# MotherBoard_ver2_2.net
KiCad netlist of a schematic drawn in EAGLE
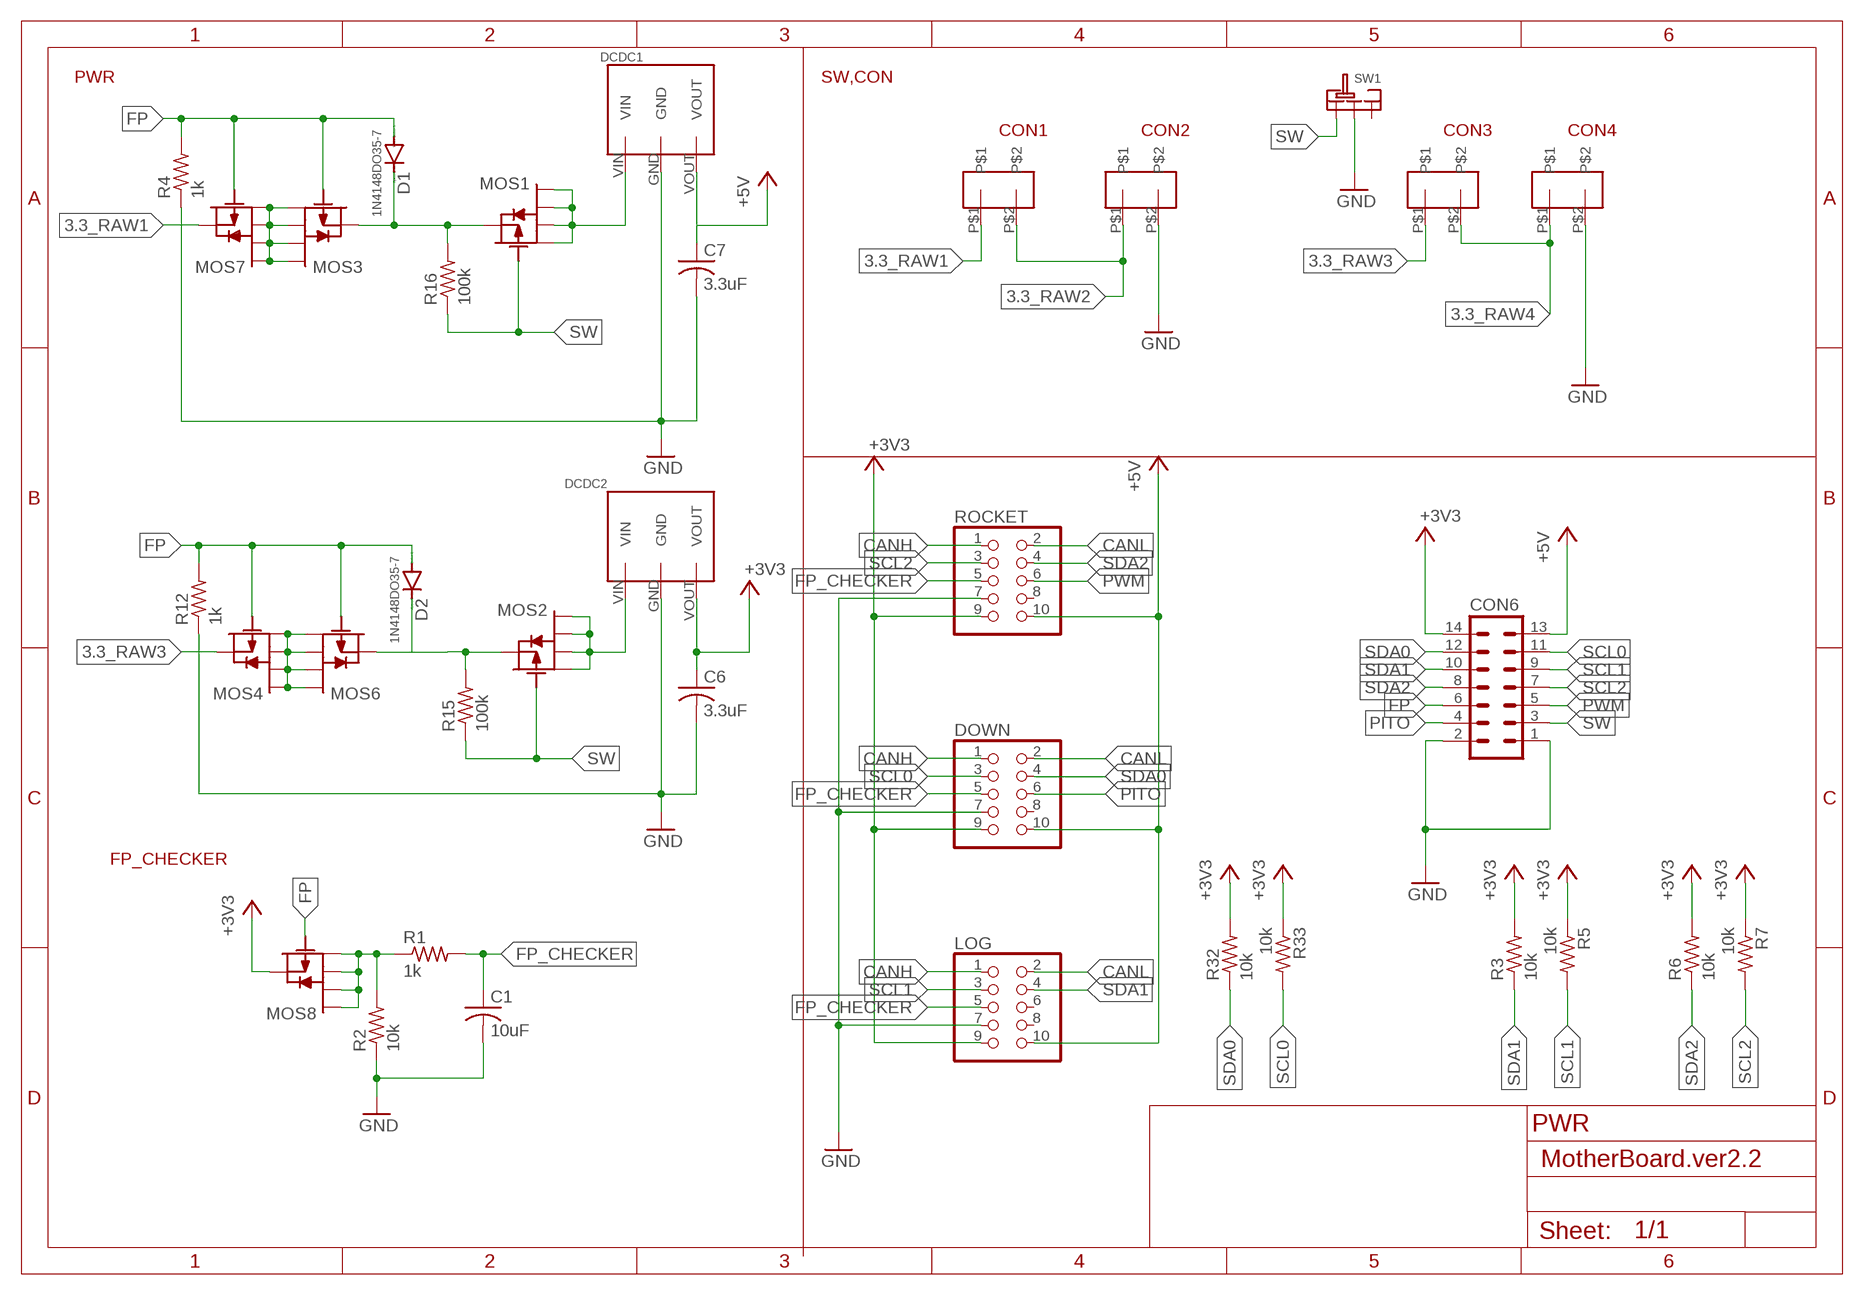
[diagram p0: schematic, sheet 1]

(export (version "E")
  (design (tool "Eeschema 10.0.6"))
  (components
    (comp (ref "C1")
      (value "10uF")
      (footprint "eagle-import:C0603")
      (libsource (lib "eagle-import") (part "C-USC0603"))
    )
    (comp (ref "C6")
      (value "3.3uF")
      (footprint "eagle-import:C0603")
      (libsource (lib "eagle-import") (part "C-USC0603"))
    )
    (comp (ref "C7")
      (value "3.3uF")
      (footprint "eagle-import:C0603")
      (libsource (lib "eagle-import") (part "C-USC0603"))
    )
    (comp (ref "CON1")
      (value "1.25CON2PIN")
      (footprint "eagle-import:1.25CON2PIN")
      (libsource (lib "eagle-import") (part "1.25CON2PIN"))
    )
    (comp (ref "CON2")
      (value "1.25CON2PIN")
      (footprint "eagle-import:1.25CON2PIN")
      (libsource (lib "eagle-import") (part "1.25CON2PIN"))
    )
    (comp (ref "CON3")
      (value "1.25CON2PIN")
      (footprint "eagle-import:1.25CON2PIN")
      (libsource (lib "eagle-import") (part "1.25CON2PIN"))
    )
    (comp (ref "CON4")
      (value "1.25CON2PIN")
      (footprint "eagle-import:1.25CON2PIN")
      (libsource (lib "eagle-import") (part "1.25CON2PIN"))
    )
    (comp (ref "CON6")
      (value "ML14L")
      (footprint "eagle-import:ML14L")
      (libsource (lib "eagle-import") (part "ML14L"))
    )
    (comp (ref "D1")
      (value "1N4148DO35-7")
      (footprint "eagle-import:DO35-7")
      (libsource (lib "eagle-import") (part "1N4148DO35-7"))
    )
    (comp (ref "D2")
      (value "1N4148DO35-7")
      (footprint "eagle-import:DO35-7")
      (libsource (lib "eagle-import") (part "1N4148DO35-7"))
    )
    (comp (ref "DCDC1")
      (value "5V1A_M78AR05-1")
      (footprint "eagle-import:5V1A_M78AR05-1")
      (libsource (lib "eagle-import") (part "5V1A_M78AR05-1"))
    )
    (comp (ref "DCDC2")
      (value "3.3V1A_M78AR033-1")
      (footprint "eagle-import:3.3V1A_M78AR033-1")
      (libsource (lib "eagle-import") (part "3.3V1A_M78AR033-1"))
    )
    (comp (ref "DOWN")
      (value "PINHD-2X5")
      (footprint "eagle-import:2X05")
      (libsource (lib "eagle-import") (part "PINHD-2X5"))
    )
    (comp (ref "LOG")
      (value "PINHD-2X5")
      (footprint "eagle-import:2X05")
      (libsource (lib "eagle-import") (part "PINHD-2X5"))
    )
    (comp (ref "MOS1")
      (value "PCH_SSM6J808R")
      (footprint "eagle-import:SSM6J808R")
      (libsource (lib "eagle-import") (part "PCH_SSM6J808R"))
    )
    (comp (ref "MOS2")
      (value "PCH_SSM6J808R")
      (footprint "eagle-import:SSM6J808R")
      (libsource (lib "eagle-import") (part "PCH_SSM6J808R"))
    )
    (comp (ref "MOS3")
      (value "PCH_SSM6J808R")
      (footprint "eagle-import:SSM6J808R")
      (libsource (lib "eagle-import") (part "PCH_SSM6J808R"))
    )
    (comp (ref "MOS4")
      (value "PCH_SSM6J808R")
      (footprint "eagle-import:SSM6J808R")
      (libsource (lib "eagle-import") (part "PCH_SSM6J808R"))
    )
    (comp (ref "MOS6")
      (value "PCH_SSM6J808R")
      (footprint "eagle-import:SSM6J808R")
      (libsource (lib "eagle-import") (part "PCH_SSM6J808R"))
    )
    (comp (ref "MOS7")
      (value "PCH_SSM6J808R")
      (footprint "eagle-import:SSM6J808R")
      (libsource (lib "eagle-import") (part "PCH_SSM6J808R"))
    )
    (comp (ref "MOS8")
      (value "PCH_SSM6J808R")
      (footprint "eagle-import:SSM6J808R")
      (libsource (lib "eagle-import") (part "PCH_SSM6J808R"))
    )
    (comp (ref "R1")
      (value "1k")
      (footprint "eagle-import:R0603")
      (libsource (lib "eagle-import") (part "R-US_R0603"))
    )
    (comp (ref "R2")
      (value "10k")
      (footprint "eagle-import:R0603")
      (libsource (lib "eagle-import") (part "R-US_R0603"))
    )
    (comp (ref "R3")
      (value "10k")
      (footprint "eagle-import:R0603")
      (libsource (lib "eagle-import") (part "R-US_R0603"))
    )
    (comp (ref "R4")
      (value "1k")
      (footprint "eagle-import:R0603")
      (libsource (lib "eagle-import") (part "R-US_R0603"))
    )
    (comp (ref "R5")
      (value "10k")
      (footprint "eagle-import:R0603")
      (libsource (lib "eagle-import") (part "R-US_R0603"))
    )
    (comp (ref "R6")
      (value "10k")
      (footprint "eagle-import:R0603")
      (libsource (lib "eagle-import") (part "R-US_R0603"))
    )
    (comp (ref "R7")
      (value "10k")
      (footprint "eagle-import:R0603")
      (libsource (lib "eagle-import") (part "R-US_R0603"))
    )
    (comp (ref "R12")
      (value "1k")
      (footprint "eagle-import:R0603")
      (libsource (lib "eagle-import") (part "R-US_R0603"))
    )
    (comp (ref "R15")
      (value "100k")
      (footprint "eagle-import:R0603")
      (libsource (lib "eagle-import") (part "R-US_R0603"))
    )
    (comp (ref "R16")
      (value "100k")
      (footprint "eagle-import:R0603")
      (libsource (lib "eagle-import") (part "R-US_R0603"))
    )
    (comp (ref "R32")
      (value "10k")
      (footprint "eagle-import:R0603")
      (libsource (lib "eagle-import") (part "R-US_R0603"))
    )
    (comp (ref "R33")
      (value "10k")
      (footprint "eagle-import:R0603")
      (libsource (lib "eagle-import") (part "R-US_R0603"))
    )
    (comp (ref "ROCKET")
      (value "PINHD-2X5")
      (footprint "eagle-import:2X05")
      (libsource (lib "eagle-import") (part "PINHD-2X5"))
    )
    (comp (ref "SW1")
      (value "SRIDE_SWITCH")
      (footprint "eagle-import:SRIDE_SWITCH")
      (libsource (lib "eagle-import") (part "SRIDE_SWITCH"))
    )
  )
  (nets
    (net (code "1") (name "+3V3") (class "Default")
      (node (ref "C6") (pin "1") (pinfunction "1_1") (pintype "passive"))
      (node (ref "CON6") (pin "14") (pinfunction "14_14") (pintype "passive"))
      (node (ref "DCDC2") (pin "VOUT") (pinfunction "VOUT_VOUT") (pintype "bidirectional"))
      (node (ref "DOWN") (pin "9") (pinfunction "9_9") (pintype "passive"))
      (node (ref "LOG") (pin "9") (pinfunction "9_9") (pintype "passive"))
      (node (ref "MOS8") (pin "4") (pinfunction "4_4") (pintype "bidirectional"))
      (node (ref "R3") (pin "2") (pinfunction "2_2") (pintype "passive"))
      (node (ref "R32") (pin "2") (pinfunction "2_2") (pintype "passive"))
      (node (ref "R33") (pin "1") (pinfunction "1_1") (pintype "passive"))
      (node (ref "R5") (pin "1") (pinfunction "1_1") (pintype "passive"))
      (node (ref "R6") (pin "2") (pinfunction "2_2") (pintype "passive"))
      (node (ref "R7") (pin "1") (pinfunction "1_1") (pintype "passive"))
      (node (ref "ROCKET") (pin "9") (pinfunction "9_9") (pintype "passive"))
    )
    (net (code "2") (name "+5V") (class "Default")
      (node (ref "C7") (pin "1") (pinfunction "1_1") (pintype "passive"))
      (node (ref "CON6") (pin "13") (pinfunction "13_13") (pintype "passive"))
      (node (ref "DCDC1") (pin "VOUT") (pinfunction "VOUT_VOUT") (pintype "bidirectional"))
      (node (ref "DOWN") (pin "10") (pinfunction "10_10") (pintype "passive"))
      (node (ref "LOG") (pin "10") (pinfunction "10_10") (pintype "passive"))
      (node (ref "ROCKET") (pin "10") (pinfunction "10_10") (pintype "passive"))
    )
    (net (code "3") (name "3.3_RAW1") (class "Default")
      (node (ref "CON1") (pin "P$1") (pinfunction "P$1_P$1") (pintype "bidirectional"))
      (node (ref "MOS7") (pin "4") (pinfunction "4_4") (pintype "bidirectional"))
    )
    (net (code "4") (name "3.3_RAW2") (class "Default")
      (node (ref "CON1") (pin "P$2") (pinfunction "P$2_P$2") (pintype "bidirectional"))
      (node (ref "CON2") (pin "P$1") (pinfunction "P$1_P$1") (pintype "bidirectional"))
    )
    (net (code "5") (name "3.3_RAW3") (class "Default")
      (node (ref "CON3") (pin "P$1") (pinfunction "P$1_P$1") (pintype "bidirectional"))
      (node (ref "MOS4") (pin "4") (pinfunction "4_4") (pintype "bidirectional"))
    )
    (net (code "6") (name "3.3_RAW4") (class "Default")
      (node (ref "CON3") (pin "P$2") (pinfunction "P$2_P$2") (pintype "bidirectional"))
      (node (ref "CON4") (pin "P$1") (pinfunction "P$1_P$1") (pintype "bidirectional"))
    )
    (net (code "7") (name "CANH") (class "Default")
      (node (ref "DOWN") (pin "1") (pinfunction "1_1") (pintype "passive"))
      (node (ref "LOG") (pin "1") (pinfunction "1_1") (pintype "passive"))
      (node (ref "ROCKET") (pin "1") (pinfunction "1_1") (pintype "passive"))
    )
    (net (code "8") (name "CANL") (class "Default")
      (node (ref "DOWN") (pin "2") (pinfunction "2_2") (pintype "passive"))
      (node (ref "LOG") (pin "2") (pinfunction "2_2") (pintype "passive"))
      (node (ref "ROCKET") (pin "2") (pinfunction "2_2") (pintype "passive"))
    )
    (net (code "9") (name "FP") (class "Default")
      (node (ref "CON6") (pin "6") (pinfunction "6_6") (pintype "passive"))
      (node (ref "D1") (pin "A") (pinfunction "A_A") (pintype "passive"))
      (node (ref "D2") (pin "A") (pinfunction "A_A") (pintype "passive"))
      (node (ref "MOS3") (pin "3") (pinfunction "3_3") (pintype "bidirectional"))
      (node (ref "MOS4") (pin "3") (pinfunction "3_3") (pintype "bidirectional"))
      (node (ref "MOS6") (pin "3") (pinfunction "3_3") (pintype "bidirectional"))
      (node (ref "MOS7") (pin "3") (pinfunction "3_3") (pintype "bidirectional"))
      (node (ref "MOS8") (pin "3") (pinfunction "3_3") (pintype "bidirectional"))
      (node (ref "R12") (pin "2") (pinfunction "2_2") (pintype "passive"))
      (node (ref "R4") (pin "2") (pinfunction "2_2") (pintype "passive"))
    )
    (net (code "10") (name "FP_CHECKER") (class "Default")
      (node (ref "C1") (pin "1") (pinfunction "1_1") (pintype "passive"))
      (node (ref "DOWN") (pin "5") (pinfunction "5_5") (pintype "passive"))
      (node (ref "LOG") (pin "5") (pinfunction "5_5") (pintype "passive"))
      (node (ref "R1") (pin "2") (pinfunction "2_2") (pintype "passive"))
      (node (ref "ROCKET") (pin "5") (pinfunction "5_5") (pintype "passive"))
    )
    (net (code "11") (name "GND") (class "Default")
      (node (ref "C1") (pin "2") (pinfunction "2_2") (pintype "passive"))
      (node (ref "C6") (pin "2") (pinfunction "2_2") (pintype "passive"))
      (node (ref "C7") (pin "2") (pinfunction "2_2") (pintype "passive"))
      (node (ref "CON2") (pin "P$2") (pinfunction "P$2_P$2") (pintype "bidirectional"))
      (node (ref "CON4") (pin "P$2") (pinfunction "P$2_P$2") (pintype "bidirectional"))
      (node (ref "CON6") (pin "1") (pinfunction "1_1") (pintype "passive"))
      (node (ref "CON6") (pin "2") (pinfunction "2_2") (pintype "passive"))
      (node (ref "DCDC1") (pin "GND") (pinfunction "GND_GND") (pintype "bidirectional"))
      (node (ref "DCDC2") (pin "GND") (pinfunction "GND_GND") (pintype "bidirectional"))
      (node (ref "DOWN") (pin "7") (pinfunction "7_7") (pintype "passive"))
      (node (ref "LOG") (pin "7") (pinfunction "7_7") (pintype "passive"))
      (node (ref "R12") (pin "1") (pinfunction "1_1") (pintype "passive"))
      (node (ref "R2") (pin "1") (pinfunction "1_1") (pintype "passive"))
      (node (ref "R4") (pin "1") (pinfunction "1_1") (pintype "passive"))
      (node (ref "ROCKET") (pin "7") (pinfunction "7_7") (pintype "passive"))
      (node (ref "SW1") (pin "LR") (pinfunction "LR_LR") (pintype "bidirectional"))
    )
    (net (code "12") (name "Net-(D1-PadC)") (class "Default")
      (node (ref "D1") (pin "C") (pinfunction "C_C") (pintype "passive"))
      (node (ref "MOS1") (pin "4") (pinfunction "4_4") (pintype "bidirectional"))
      (node (ref "MOS3") (pin "4") (pinfunction "4_4") (pintype "bidirectional"))
      (node (ref "R16") (pin "2") (pinfunction "2_2") (pintype "passive"))
    )
    (net (code "13") (name "Net-(D2-PadC)") (class "Default")
      (node (ref "D2") (pin "C") (pinfunction "C_C") (pintype "passive"))
      (node (ref "MOS2") (pin "4") (pinfunction "4_4") (pintype "bidirectional"))
      (node (ref "MOS6") (pin "4") (pinfunction "4_4") (pintype "bidirectional"))
      (node (ref "R15") (pin "2") (pinfunction "2_2") (pintype "passive"))
    )
    (net (code "14") (name "Net-(DCDC1-PadVIN)") (class "Default")
      (node (ref "DCDC1") (pin "VIN") (pinfunction "VIN_VIN") (pintype "bidirectional"))
      (node (ref "MOS1") (pin "1") (pinfunction "1_1") (pintype "bidirectional"))
      (node (ref "MOS1") (pin "2") (pinfunction "2_2") (pintype "bidirectional"))
      (node (ref "MOS1") (pin "5") (pinfunction "5_5") (pintype "bidirectional"))
      (node (ref "MOS1") (pin "6") (pinfunction "6_6") (pintype "bidirectional"))
    )
    (net (code "15") (name "Net-(DCDC2-PadVIN)") (class "Default")
      (node (ref "DCDC2") (pin "VIN") (pinfunction "VIN_VIN") (pintype "bidirectional"))
      (node (ref "MOS2") (pin "1") (pinfunction "1_1") (pintype "bidirectional"))
      (node (ref "MOS2") (pin "2") (pinfunction "2_2") (pintype "bidirectional"))
      (node (ref "MOS2") (pin "5") (pinfunction "5_5") (pintype "bidirectional"))
      (node (ref "MOS2") (pin "6") (pinfunction "6_6") (pintype "bidirectional"))
    )
    (net (code "16") (name "Net-(MOS3-Pad1)") (class "Default")
      (node (ref "MOS3") (pin "1") (pinfunction "1_1") (pintype "bidirectional"))
      (node (ref "MOS3") (pin "2") (pinfunction "2_2") (pintype "bidirectional"))
      (node (ref "MOS3") (pin "5") (pinfunction "5_5") (pintype "bidirectional"))
      (node (ref "MOS3") (pin "6") (pinfunction "6_6") (pintype "bidirectional"))
      (node (ref "MOS7") (pin "1") (pinfunction "1_1") (pintype "bidirectional"))
      (node (ref "MOS7") (pin "2") (pinfunction "2_2") (pintype "bidirectional"))
      (node (ref "MOS7") (pin "5") (pinfunction "5_5") (pintype "bidirectional"))
      (node (ref "MOS7") (pin "6") (pinfunction "6_6") (pintype "bidirectional"))
    )
    (net (code "17") (name "Net-(MOS4-Pad1)") (class "Default")
      (node (ref "MOS4") (pin "1") (pinfunction "1_1") (pintype "bidirectional"))
      (node (ref "MOS4") (pin "2") (pinfunction "2_2") (pintype "bidirectional"))
      (node (ref "MOS4") (pin "5") (pinfunction "5_5") (pintype "bidirectional"))
      (node (ref "MOS4") (pin "6") (pinfunction "6_6") (pintype "bidirectional"))
      (node (ref "MOS6") (pin "1") (pinfunction "1_1") (pintype "bidirectional"))
      (node (ref "MOS6") (pin "2") (pinfunction "2_2") (pintype "bidirectional"))
      (node (ref "MOS6") (pin "5") (pinfunction "5_5") (pintype "bidirectional"))
      (node (ref "MOS6") (pin "6") (pinfunction "6_6") (pintype "bidirectional"))
    )
    (net (code "18") (name "Net-(MOS8-Pad1)") (class "Default")
      (node (ref "MOS8") (pin "1") (pinfunction "1_1") (pintype "bidirectional"))
      (node (ref "MOS8") (pin "2") (pinfunction "2_2") (pintype "bidirectional"))
      (node (ref "MOS8") (pin "5") (pinfunction "5_5") (pintype "bidirectional"))
      (node (ref "MOS8") (pin "6") (pinfunction "6_6") (pintype "bidirectional"))
      (node (ref "R1") (pin "1") (pinfunction "1_1") (pintype "passive"))
      (node (ref "R2") (pin "2") (pinfunction "2_2") (pintype "passive"))
    )
    (net (code "19") (name "PITO") (class "Default")
      (node (ref "CON6") (pin "4") (pinfunction "4_4") (pintype "passive"))
      (node (ref "DOWN") (pin "6") (pinfunction "6_6") (pintype "passive"))
    )
    (net (code "20") (name "PWM") (class "Default")
      (node (ref "CON6") (pin "5") (pinfunction "5_5") (pintype "passive"))
      (node (ref "ROCKET") (pin "6") (pinfunction "6_6") (pintype "passive"))
    )
    (net (code "21") (name "SCL0") (class "Default")
      (node (ref "CON6") (pin "11") (pinfunction "11_11") (pintype "passive"))
      (node (ref "DOWN") (pin "3") (pinfunction "3_3") (pintype "passive"))
      (node (ref "R33") (pin "2") (pinfunction "2_2") (pintype "passive"))
    )
    (net (code "22") (name "SCL1") (class "Default")
      (node (ref "CON6") (pin "9") (pinfunction "9_9") (pintype "passive"))
      (node (ref "LOG") (pin "3") (pinfunction "3_3") (pintype "passive"))
      (node (ref "R5") (pin "2") (pinfunction "2_2") (pintype "passive"))
    )
    (net (code "23") (name "SCL2") (class "Default")
      (node (ref "CON6") (pin "7") (pinfunction "7_7") (pintype "passive"))
      (node (ref "R7") (pin "2") (pinfunction "2_2") (pintype "passive"))
      (node (ref "ROCKET") (pin "3") (pinfunction "3_3") (pintype "passive"))
    )
    (net (code "24") (name "SDA0") (class "Default")
      (node (ref "CON6") (pin "12") (pinfunction "12_12") (pintype "passive"))
      (node (ref "DOWN") (pin "4") (pinfunction "4_4") (pintype "passive"))
      (node (ref "R32") (pin "1") (pinfunction "1_1") (pintype "passive"))
    )
    (net (code "25") (name "SDA1") (class "Default")
      (node (ref "CON6") (pin "10") (pinfunction "10_10") (pintype "passive"))
      (node (ref "LOG") (pin "4") (pinfunction "4_4") (pintype "passive"))
      (node (ref "R3") (pin "1") (pinfunction "1_1") (pintype "passive"))
    )
    (net (code "26") (name "SDA2") (class "Default")
      (node (ref "CON6") (pin "8") (pinfunction "8_8") (pintype "passive"))
      (node (ref "R6") (pin "1") (pinfunction "1_1") (pintype "passive"))
      (node (ref "ROCKET") (pin "4") (pinfunction "4_4") (pintype "passive"))
    )
    (net (code "27") (name "SW") (class "Default")
      (node (ref "CON6") (pin "3") (pinfunction "3_3") (pintype "passive"))
      (node (ref "MOS1") (pin "3") (pinfunction "3_3") (pintype "bidirectional"))
      (node (ref "MOS2") (pin "3") (pinfunction "3_3") (pintype "bidirectional"))
      (node (ref "R15") (pin "1") (pinfunction "1_1") (pintype "passive"))
      (node (ref "R16") (pin "1") (pinfunction "1_1") (pintype "passive"))
      (node (ref "SW1") (pin "L") (pinfunction "L_L") (pintype "bidirectional"))
    )
    (net (code "28") (name "unconnected-(DOWN-Pad8)") (class "Default")
      (node (ref "DOWN") (pin "8") (pinfunction "8_8") (pintype "passive"))
    )
    (net (code "29") (name "unconnected-(LOG-Pad6)") (class "Default")
      (node (ref "LOG") (pin "6") (pinfunction "6_6") (pintype "passive"))
    )
    (net (code "30") (name "unconnected-(LOG-Pad8)") (class "Default")
      (node (ref "LOG") (pin "8") (pinfunction "8_8") (pintype "passive"))
    )
    (net (code "31") (name "unconnected-(ROCKET-Pad8)") (class "Default")
      (node (ref "ROCKET") (pin "8") (pinfunction "8_8") (pintype "passive"))
    )
    (net (code "32") (name "unconnected-(SW1-PadR)") (class "Default")
      (node (ref "SW1") (pin "R") (pinfunction "R_R") (pintype "bidirectional"))
    )
  )
)
